# LCD_SDCARD.net
KiCad netlist of a schematic drawn in Altium Designer
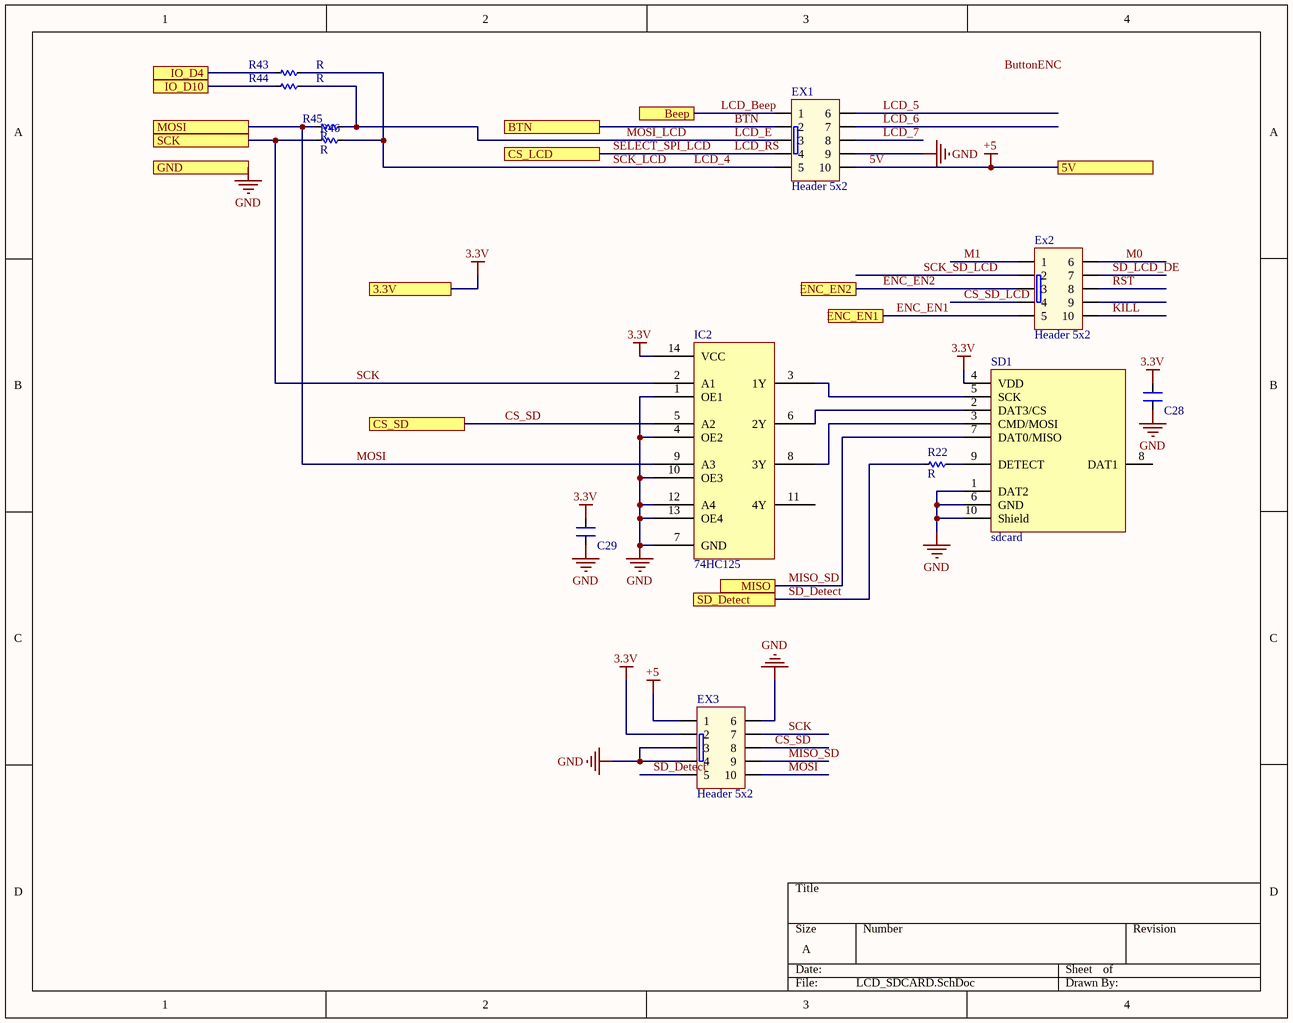
[diagram p0: LCD_SDCARD.SchDoc]

(export (version "E")
  (design (tool "Eeschema 10.0.6"))
  (components
    (comp (ref "C28") (value "CN") (footprint "CN-SMD-0603_big") (libsource (lib "nhan") (part "CN")))
    (comp (ref "C29") (value "CN") (footprint "CN-SMD-0603_big") (libsource (lib "nhan") (part "CN")))
    (comp (ref "EX1")
      (value "Header 5x2")
      (footprint "Hed2X5")
      (libsource (lib "syhaunguyen") (part "HED5x2"))
    )
    (comp (ref "Ex2")
      (value "Header 5x2")
      (footprint "Hed2X5")
      (libsource (lib "syhaunguyen") (part "HED5x2"))
    )
    (comp (ref "EX3")
      (value "Header 5x2")
      (footprint "Hed2X5")
      (libsource (lib "syhaunguyen") (part "HED5x2"))
    )
    (comp (ref "IC2") (value "74HC125") (footprint "SO14") (libsource (lib "nhan") (part "74HC125")))
    (comp (ref "R22") (value "R") (footprint "RES-SMD-0603_BIG") (libsource (lib "nhan") (part "R")))
    (comp (ref "R43") (value "R") (footprint "RES-SMD-0603_BIG") (libsource (lib "nhan") (part "R")))
    (comp (ref "R44") (value "R") (footprint "RES-SMD-0603_BIG") (libsource (lib "nhan") (part "R")))
    (comp (ref "R45") (value "R") (footprint "RES-SMD-0603_BIG") (libsource (lib "nhan") (part "R")))
    (comp (ref "R46") (value "R") (footprint "RES-SMD-0603_BIG") (libsource (lib "nhan") (part "R")))
    (comp (ref "SD1")
      (value "sdcard")
      (footprint "microSD™ Card_TF")
      (libsource (lib "nhan") (part "sdcard"))
    )
  )
  (nets
    (net (code "1") (name "+5") (class "Default")
      (node (ref "EX1") (pin "10") (pinfunction "10_10") (pintype "passive"))
      (node (ref "EX3") (pin "1") (pinfunction "1_1") (pintype "passive"))
    )
    (net (code "2") (name "/BTN") (class "Default")
      (node (ref "EX1") (pin "2") (pinfunction "2_2") (pintype "passive"))
    )
    (net (code "4") (name "/CS_SD") (class "Default")
      (node (ref "EX3") (pin "8") (pinfunction "8_8") (pintype "passive"))
      (node (ref "IC2") (pin "5") (pinfunction "A2_5") (pintype "passive"))
    )
    (net (code "5") (name "/CS_SD_LCD") (class "Default")
      (node (ref "Ex2") (pin "4") (pinfunction "4_4") (pintype "passive"))
    )
    (net (code "6") (name "/ENC_EN1") (class "Default")
      (node (ref "Ex2") (pin "5") (pinfunction "5_5") (pintype "passive"))
    )
    (net (code "7") (name "/ENC_EN2") (class "Default")
      (node (ref "Ex2") (pin "3") (pinfunction "3_3") (pintype "passive"))
    )
    (net (code "8") (name "/IO_D4") (class "Default")
      (node (ref "R43") (pin "2") (pinfunction "2_2") (pintype "passive"))
    )
    (net (code "9") (name "/IO_D10") (class "Default")
      (node (ref "R44") (pin "2") (pinfunction "2_2") (pintype "passive"))
    )
    (net (code "10") (name "/KILL") (class "Default")
      (node (ref "Ex2") (pin "10") (pinfunction "10_10") (pintype "passive"))
    )
    (net (code "11") (name "/LCD_4") (class "Default")
      (node (ref "EX1") (pin "5") (pinfunction "5_5") (pintype "passive"))
      (node (ref "R43") (pin "1") (pinfunction "1_1") (pintype "passive"))
      (node (ref "R46") (pin "1") (pinfunction "1_1") (pintype "passive"))
    )
    (net (code "12") (name "/LCD_5") (class "Default")
      (node (ref "EX1") (pin "6") (pinfunction "6_6") (pintype "passive"))
    )
    (net (code "13") (name "/LCD_6") (class "Default")
      (node (ref "EX1") (pin "7") (pinfunction "7_7") (pintype "passive"))
    )
    (net (code "14") (name "/LCD_7") (class "Default")
      (node (ref "EX1") (pin "8") (pinfunction "8_8") (pintype "passive"))
    )
    (net (code "15") (name "/LCD_Beep") (class "Default")
      (node (ref "EX1") (pin "1") (pinfunction "1_1") (pintype "passive"))
    )
    (net (code "16") (name "/LCD_E") (class "Default")
      (node (ref "EX1") (pin "3") (pinfunction "3_3") (pintype "passive"))
      (node (ref "R44") (pin "1") (pinfunction "1_1") (pintype "passive"))
      (node (ref "R45") (pin "1") (pinfunction "1_1") (pintype "passive"))
    )
    (net (code "17") (name "/LCD_RS") (class "Default")
      (node (ref "EX1") (pin "4") (pinfunction "4_4") (pintype "passive"))
    )
    (net (code "18") (name "/M0") (class "Default")
      (node (ref "Ex2") (pin "6") (pinfunction "6_6") (pintype "passive"))
    )
    (net (code "19") (name "/M1") (class "Default")
      (node (ref "Ex2") (pin "1") (pinfunction "1_1") (pintype "passive"))
    )
    (net (code "20") (name "/MISO_SD") (class "Default")
      (node (ref "EX3") (pin "9") (pinfunction "9_9") (pintype "passive"))
      (node (ref "SD1") (pin "7") (pinfunction "DAT0/MISO_7") (pintype "passive"))
    )
    (net (code "21") (name "/MOSI") (class "Default")
      (node (ref "EX3") (pin "10") (pinfunction "10_10") (pintype "passive"))
      (node (ref "IC2") (pin "9") (pinfunction "A3_9") (pintype "passive"))
      (node (ref "R45") (pin "2") (pinfunction "2_2") (pintype "passive"))
    )
    (net (code "22") (name "/RST") (class "Default")
      (node (ref "Ex2") (pin "8") (pinfunction "8_8") (pintype "passive"))
    )
    (net (code "23") (name "/SCK") (class "Default")
      (node (ref "EX3") (pin "7") (pinfunction "7_7") (pintype "passive"))
      (node (ref "IC2") (pin "2") (pinfunction "A1_2") (pintype "passive"))
      (node (ref "R46") (pin "2") (pinfunction "2_2") (pintype "passive"))
    )
    (net (code "24") (name "/SCK_SD_LCD") (class "Default")
      (node (ref "Ex2") (pin "2") (pinfunction "2_2") (pintype "passive"))
    )
    (net (code "25") (name "/SD_Detect") (class "Default")
      (node (ref "EX3") (pin "5") (pinfunction "5_5") (pintype "passive"))
      (node (ref "R22") (pin "2") (pinfunction "2_2") (pintype "passive"))
    )
    (net (code "26") (name "/SD_LCD_DE") (class "Default")
      (node (ref "Ex2") (pin "7") (pinfunction "7_7") (pintype "passive"))
    )
    (net (code "27") (name "3.3V") (class "Default")
      (node (ref "C28") (pin "2") (pinfunction "2_2") (pintype "passive"))
      (node (ref "C29") (pin "2") (pinfunction "2_2") (pintype "passive"))
      (node (ref "EX3") (pin "2") (pinfunction "2_2") (pintype "passive"))
      (node (ref "IC2") (pin "14") (pinfunction "VCC_14") (pintype "passive"))
      (node (ref "SD1") (pin "4") (pinfunction "VDD_4") (pintype "passive"))
    )
    (net (code "28") (name "GND") (class "Default")
      (node (ref "C28") (pin "1") (pinfunction "1_1") (pintype "passive"))
      (node (ref "C29") (pin "1") (pinfunction "1_1") (pintype "passive"))
      (node (ref "EX1") (pin "9") (pinfunction "9_9") (pintype "passive"))
      (node (ref "EX3") (pin "3") (pinfunction "3_3") (pintype "passive"))
      (node (ref "EX3") (pin "4") (pinfunction "4_4") (pintype "passive"))
      (node (ref "EX3") (pin "6") (pinfunction "6_6") (pintype "passive"))
      (node (ref "IC2") (pin "1") (pinfunction "OE1_1") (pintype "passive"))
      (node (ref "IC2") (pin "10") (pinfunction "OE3_10") (pintype "passive"))
      (node (ref "IC2") (pin "12") (pinfunction "A4_12") (pintype "passive"))
      (node (ref "IC2") (pin "13") (pinfunction "OE4_13") (pintype "passive"))
      (node (ref "IC2") (pin "4") (pinfunction "OE2_4") (pintype "passive"))
      (node (ref "IC2") (pin "7") (pinfunction "GND_7") (pintype "passive"))
      (node (ref "SD1") (pin "1") (pinfunction "DAT2_1") (pintype "passive"))
      (node (ref "SD1") (pin "10") (pinfunction "Shield_10") (pintype "passive"))
      (node (ref "SD1") (pin "6") (pinfunction "GND_6") (pintype "passive"))
    )
    (net (code "29") (name "Net-(IC2-1Y)") (class "Default")
      (node (ref "IC2") (pin "3") (pinfunction "1Y_3") (pintype "passive"))
      (node (ref "SD1") (pin "5") (pinfunction "SCK_5") (pintype "passive"))
    )
    (net (code "30") (name "Net-(IC2-2Y)") (class "Default")
      (node (ref "IC2") (pin "6") (pinfunction "2Y_6") (pintype "passive"))
      (node (ref "SD1") (pin "2") (pinfunction "DAT3/CS_2") (pintype "passive"))
    )
    (net (code "31") (name "Net-(IC2-3Y)") (class "Default")
      (node (ref "IC2") (pin "8") (pinfunction "3Y_8") (pintype "passive"))
      (node (ref "SD1") (pin "3") (pinfunction "CMD/MOSI_3") (pintype "passive"))
    )
    (net (code "32") (name "Net-(SD1-DETECT)") (class "Default")
      (node (ref "R22") (pin "1") (pinfunction "1_1") (pintype "passive"))
      (node (ref "SD1") (pin "9") (pinfunction "DETECT_9") (pintype "passive"))
    )
    (net (code "33") (name "unconnected-(Ex2-Pad9)") (class "Default")
      (node (ref "Ex2") (pin "9") (pinfunction "9_9") (pintype "passive"))
    )
    (net (code "34") (name "unconnected-(IC2-4Y-Pad11)") (class "Default")
      (node (ref "IC2") (pin "11") (pinfunction "4Y_11") (pintype "passive"))
    )
    (net (code "35") (name "unconnected-(SD1-DAT1-Pad8)") (class "Default")
      (node (ref "SD1") (pin "8") (pinfunction "DAT1_8") (pintype "passive"))
    )
  )
)
